# 08_-_LUX_LED_BOARD_CONN.net
KiCad netlist of a schematic drawn in Altium Designer
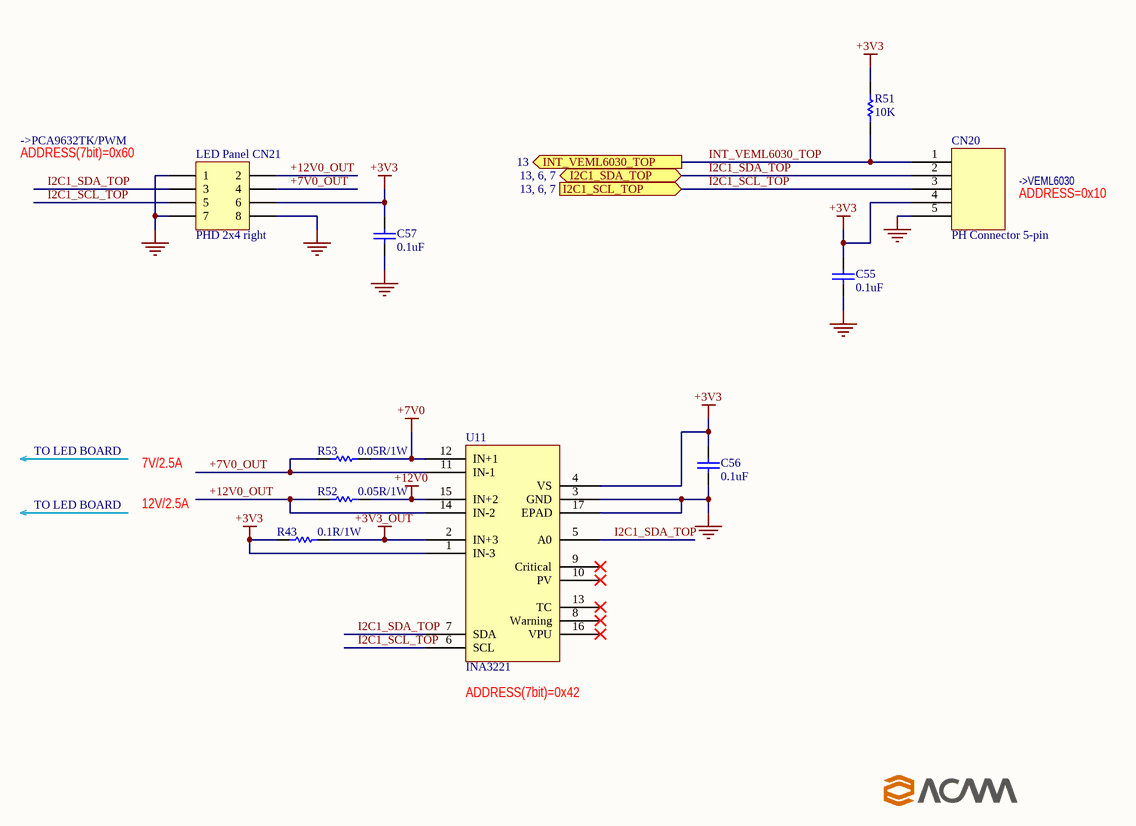
[diagram p0: [08] - LUX, LED_BOARD CONN.SchDoc]

(export (version "E")
  (design (tool "Eeschema 10.0.6"))
  (components
    (comp (ref "C55")
      (value "0.1uF")
      (footprint "0805_C_AUTO")
      (description "Non-Pol SMD Capacitor")
      (libsource (lib "Farzan Custom Library") (part "Cap SMD"))
    )
    (comp (ref "C56")
      (value "0.1uF")
      (footprint "0805_C_AUTO")
      (description "Non-Pol SMD Capacitor")
      (libsource (lib "Farzan Custom Library") (part "Cap SMD"))
    )
    (comp (ref "C57")
      (value "0.1uF")
      (footprint "0805_C_AUTO")
      (description "Non-Pol SMD Capacitor")
      (libsource (lib "Farzan Custom Library") (part "Cap SMD"))
    )
    (comp (ref "CN20")
      (value "PH Connector 5-pin")
      (footprint "PH_5PIN")
      (description "PH Connector , 5 pin, 2mm pitch, straight")
      (libsource (lib "Farzan Custom Library") (part "PH Connector 5-pin"))
    )
    (comp (ref "LED Panel CN21")
      (value "PHD 2x4 right")
      (footprint "PHDR_8PIN")
      (description "S8B-PHDSS, PH Double Right 2x4")
      (libsource (lib "Farzan Custom Library") (part "PHD Connector 2x4 Right"))
    )
    (comp (ref "R43")
      (value "0.1R/1W")
      (footprint "2512_R")
      (description "SMD Resistor")
      (fields (field (name "TOLERANCE") "1%") (field (name "MANUFACTURER PART NUM") "RL2512FK-070R1L"))
      (libsource (lib "Farzan Custom Library") (part "Res SMD"))
    )
    (comp (ref "R51")
      (value "10K")
      (footprint "0805_R_AUTO")
      (description "SMD Resistor")
      (fields (field (name "TOLERANCE") "5%"))
      (libsource (lib "Farzan Custom Library") (part "Res SMD"))
    )
    (comp (ref "R52")
      (value "0.05R/1W")
      (footprint "2512_R")
      (description "SMD Resistor")
      (fields (field (name "TOLERANCE") "1%") (field (name "MANUFACTURER PART NUM") "RL2512FK-070R05L"))
      (libsource (lib "Farzan Custom Library") (part "Res SMD"))
    )
    (comp (ref "R53")
      (value "0.05R/1W")
      (footprint "2512_R")
      (description "SMD Resistor")
      (fields (field (name "TOLERANCE") "1%") (field (name "MANUFACTURER PART NUM") "RL2512FK-070R05L"))
      (libsource (lib "Farzan Custom Library") (part "Res SMD"))
    )
    (comp (ref "U11")
      (value "INA3221")
      (footprint "QFN-16")
      (fields (field (name "MANUFACTURER PART NUM") "INA3221AIRGVR"))
      (libsource (lib "Farzan Custom Library") (part "INA3221"))
    )
  )
  (nets
    (net (code "1") (name "+3V3") (class "Default")
      (node (ref "C55") (pin "2") (pinfunction "2_2") (pintype "passive"))
      (node (ref "C56") (pin "2") (pinfunction "2_2") (pintype "passive"))
      (node (ref "C57") (pin "2") (pinfunction "2_2") (pintype "passive"))
      (node (ref "CN20") (pin "4") (pinfunction "4_4") (pintype "passive"))
      (node (ref "LED Panel CN21") (pin "6") (pinfunction "6_6") (pintype "passive"))
      (node (ref "R43") (pin "1") (pinfunction "1_1") (pintype "passive"))
      (node (ref "R51") (pin "1") (pinfunction "1_1") (pintype "passive"))
      (node (ref "U11") (pin "1") (pinfunction "IN-3_1") (pintype "passive"))
      (node (ref "U11") (pin "4") (pinfunction "VS_4") (pintype "power_in"))
    )
    (net (code "2") (name "+3V3_OUT") (class "Default")
      (node (ref "R43") (pin "2") (pinfunction "2_2") (pintype "passive"))
      (node (ref "U11") (pin "2") (pinfunction "IN+3_2") (pintype "passive"))
    )
    (net (code "3") (name "+7V0") (class "Default")
      (node (ref "R53") (pin "2") (pinfunction "2_2") (pintype "passive"))
      (node (ref "U11") (pin "12") (pinfunction "IN+1_12") (pintype "passive"))
    )
    (net (code "4") (name "+12V0") (class "Default")
      (node (ref "R52") (pin "2") (pinfunction "2_2") (pintype "passive"))
      (node (ref "U11") (pin "15") (pinfunction "IN+2_15") (pintype "passive"))
    )
    (net (code "5") (name "/+7V0_OUT") (class "Default")
      (node (ref "LED Panel CN21") (pin "4") (pinfunction "4_4") (pintype "passive"))
      (node (ref "R53") (pin "1") (pinfunction "1_1") (pintype "passive"))
      (node (ref "U11") (pin "11") (pinfunction "IN-1_11") (pintype "passive"))
    )
    (net (code "6") (name "/+12V0_OUT") (class "Default")
      (node (ref "LED Panel CN21") (pin "2") (pinfunction "2_2") (pintype "passive"))
      (node (ref "R52") (pin "1") (pinfunction "1_1") (pintype "passive"))
      (node (ref "U11") (pin "14") (pinfunction "IN-2_14") (pintype "passive"))
    )
    (net (code "7") (name "/I2C1_SCL_TOP") (class "Default")
      (node (ref "CN20") (pin "3") (pinfunction "3_3") (pintype "passive"))
      (node (ref "LED Panel CN21") (pin "5") (pinfunction "5_5") (pintype "passive"))
      (node (ref "U11") (pin "6") (pinfunction "SCL_6") (pintype "passive"))
    )
    (net (code "8") (name "/I2C1_SDA_TOP") (class "Default")
      (node (ref "CN20") (pin "2") (pinfunction "2_2") (pintype "passive"))
      (node (ref "LED Panel CN21") (pin "3") (pinfunction "3_3") (pintype "passive"))
      (node (ref "U11") (pin "5") (pinfunction "A0_5") (pintype "passive"))
      (node (ref "U11") (pin "7") (pinfunction "SDA_7") (pintype "passive"))
    )
    (net (code "9") (name "/INT_VEML6030_TOP") (class "Default")
      (node (ref "CN20") (pin "1") (pinfunction "1_1") (pintype "passive"))
      (node (ref "R51") (pin "2") (pinfunction "2_2") (pintype "passive"))
    )
    (net (code "10") (name "GND") (class "Default")
      (node (ref "C55") (pin "1") (pinfunction "1_1") (pintype "passive"))
      (node (ref "C56") (pin "1") (pinfunction "1_1") (pintype "passive"))
      (node (ref "C57") (pin "1") (pinfunction "1_1") (pintype "passive"))
      (node (ref "CN20") (pin "5") (pinfunction "5_5") (pintype "passive"))
      (node (ref "LED Panel CN21") (pin "1") (pinfunction "1_1") (pintype "passive"))
      (node (ref "LED Panel CN21") (pin "7") (pinfunction "7_7") (pintype "passive"))
      (node (ref "LED Panel CN21") (pin "8") (pinfunction "8_8") (pintype "passive"))
      (node (ref "U11") (pin "17") (pinfunction "EPAD_17") (pintype "passive"))
      (node (ref "U11") (pin "3") (pinfunction "GND_3") (pintype "power_in"))
    )
    (net (code "11") (name "unconnected-(U11-Critical-Pad9)") (class "Default")
      (node (ref "U11") (pin "9") (pinfunction "Critical_9") (pintype "passive+no_connect"))
    )
    (net (code "12") (name "unconnected-(U11-PV-Pad10)") (class "Default")
      (node (ref "U11") (pin "10") (pinfunction "PV_10") (pintype "passive+no_connect"))
    )
    (net (code "13") (name "unconnected-(U11-TC-Pad13)") (class "Default")
      (node (ref "U11") (pin "13") (pinfunction "TC_13") (pintype "passive+no_connect"))
    )
    (net (code "14") (name "unconnected-(U11-VPU-Pad16)") (class "Default")
      (node (ref "U11") (pin "16") (pinfunction "VPU_16") (pintype "passive+no_connect"))
    )
    (net (code "15") (name "unconnected-(U11-Warning-Pad8)") (class "Default")
      (node (ref "U11") (pin "8") (pinfunction "Warning_8") (pintype "passive+no_connect"))
    )
  )
)
